# ISPbreadboardAdapter_ATmega328compatible.net
KiCad netlist of a schematic drawn in EAGLE
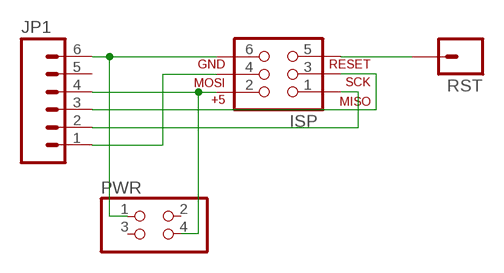
[diagram p0: schematic, sheet 1]

(export (version "E")
  (design (tool "Eeschema 10.0.6"))
  (components
    (comp (ref "ISP")
      (value "AVR_SPI_PRG_6PTH")
      (footprint "eagle-import:2X3")
      (libsource (lib "eagle-import") (part "AVR_SPI_PRG_6PTH"))
    )
    (comp (ref "JP1")
      (value "M06SILK_FEMALE_PTH")
      (footprint "eagle-import:1X06")
      (libsource (lib "eagle-import") (part "M06SILK_FEMALE_PTH"))
    )
    (comp (ref "PWR")
      (value "PINHD-2X2")
      (footprint "eagle-import:2X02")
      (libsource (lib "eagle-import") (part "PINHD-2X2"))
    )
    (comp (ref "RST")
      (value "M01PTH")
      (footprint "eagle-import:1X01")
      (libsource (lib "eagle-import") (part "M01PTH"))
    )
  )
  (nets
    (net (code "1") (name "Net-(ISP-Pad1)") (class "Default")
      (node (ref "ISP") (pin "1") (pinfunction "1_1") (pintype "passive"))
      (node (ref "JP1") (pin "2") (pinfunction "2_2") (pintype "passive"))
    )
    (net (code "2") (name "Net-(ISP-Pad2)") (class "Default")
      (node (ref "ISP") (pin "2") (pinfunction "2_2") (pintype "passive"))
      (node (ref "JP1") (pin "4") (pinfunction "4_4") (pintype "passive"))
      (node (ref "PWR") (pin "4") (pinfunction "4_4") (pintype "passive"))
    )
    (net (code "3") (name "Net-(ISP-Pad3)") (class "Default")
      (node (ref "ISP") (pin "3") (pinfunction "3_3") (pintype "passive"))
      (node (ref "JP1") (pin "3") (pinfunction "3_3") (pintype "passive"))
    )
    (net (code "4") (name "Net-(ISP-Pad4)") (class "Default")
      (node (ref "ISP") (pin "4") (pinfunction "4_4") (pintype "passive"))
      (node (ref "JP1") (pin "1") (pinfunction "1_1") (pintype "passive"))
    )
    (net (code "5") (name "Net-(ISP-Pad5)") (class "Default")
      (node (ref "ISP") (pin "5") (pinfunction "5_5") (pintype "passive"))
      (node (ref "RST") (pin "1") (pinfunction "1_1") (pintype "passive"))
    )
    (net (code "6") (name "Net-(ISP-Pad6)") (class "Default")
      (node (ref "ISP") (pin "6") (pinfunction "6_6") (pintype "passive"))
      (node (ref "JP1") (pin "6") (pinfunction "6_6") (pintype "passive"))
      (node (ref "PWR") (pin "1") (pinfunction "1_1") (pintype "passive"))
    )
    (net (code "7") (name "unconnected-(JP1-Pad5)") (class "Default")
      (node (ref "JP1") (pin "5") (pinfunction "5_5") (pintype "passive"))
    )
    (net (code "8") (name "unconnected-(PWR-Pad2)") (class "Default")
      (node (ref "PWR") (pin "2") (pinfunction "2_2") (pintype "passive"))
    )
    (net (code "9") (name "unconnected-(PWR-Pad3)") (class "Default")
      (node (ref "PWR") (pin "3") (pinfunction "3_3") (pintype "passive"))
    )
  )
)
